# Sheet1.net
KiCad netlist of a schematic drawn in Altium Designer
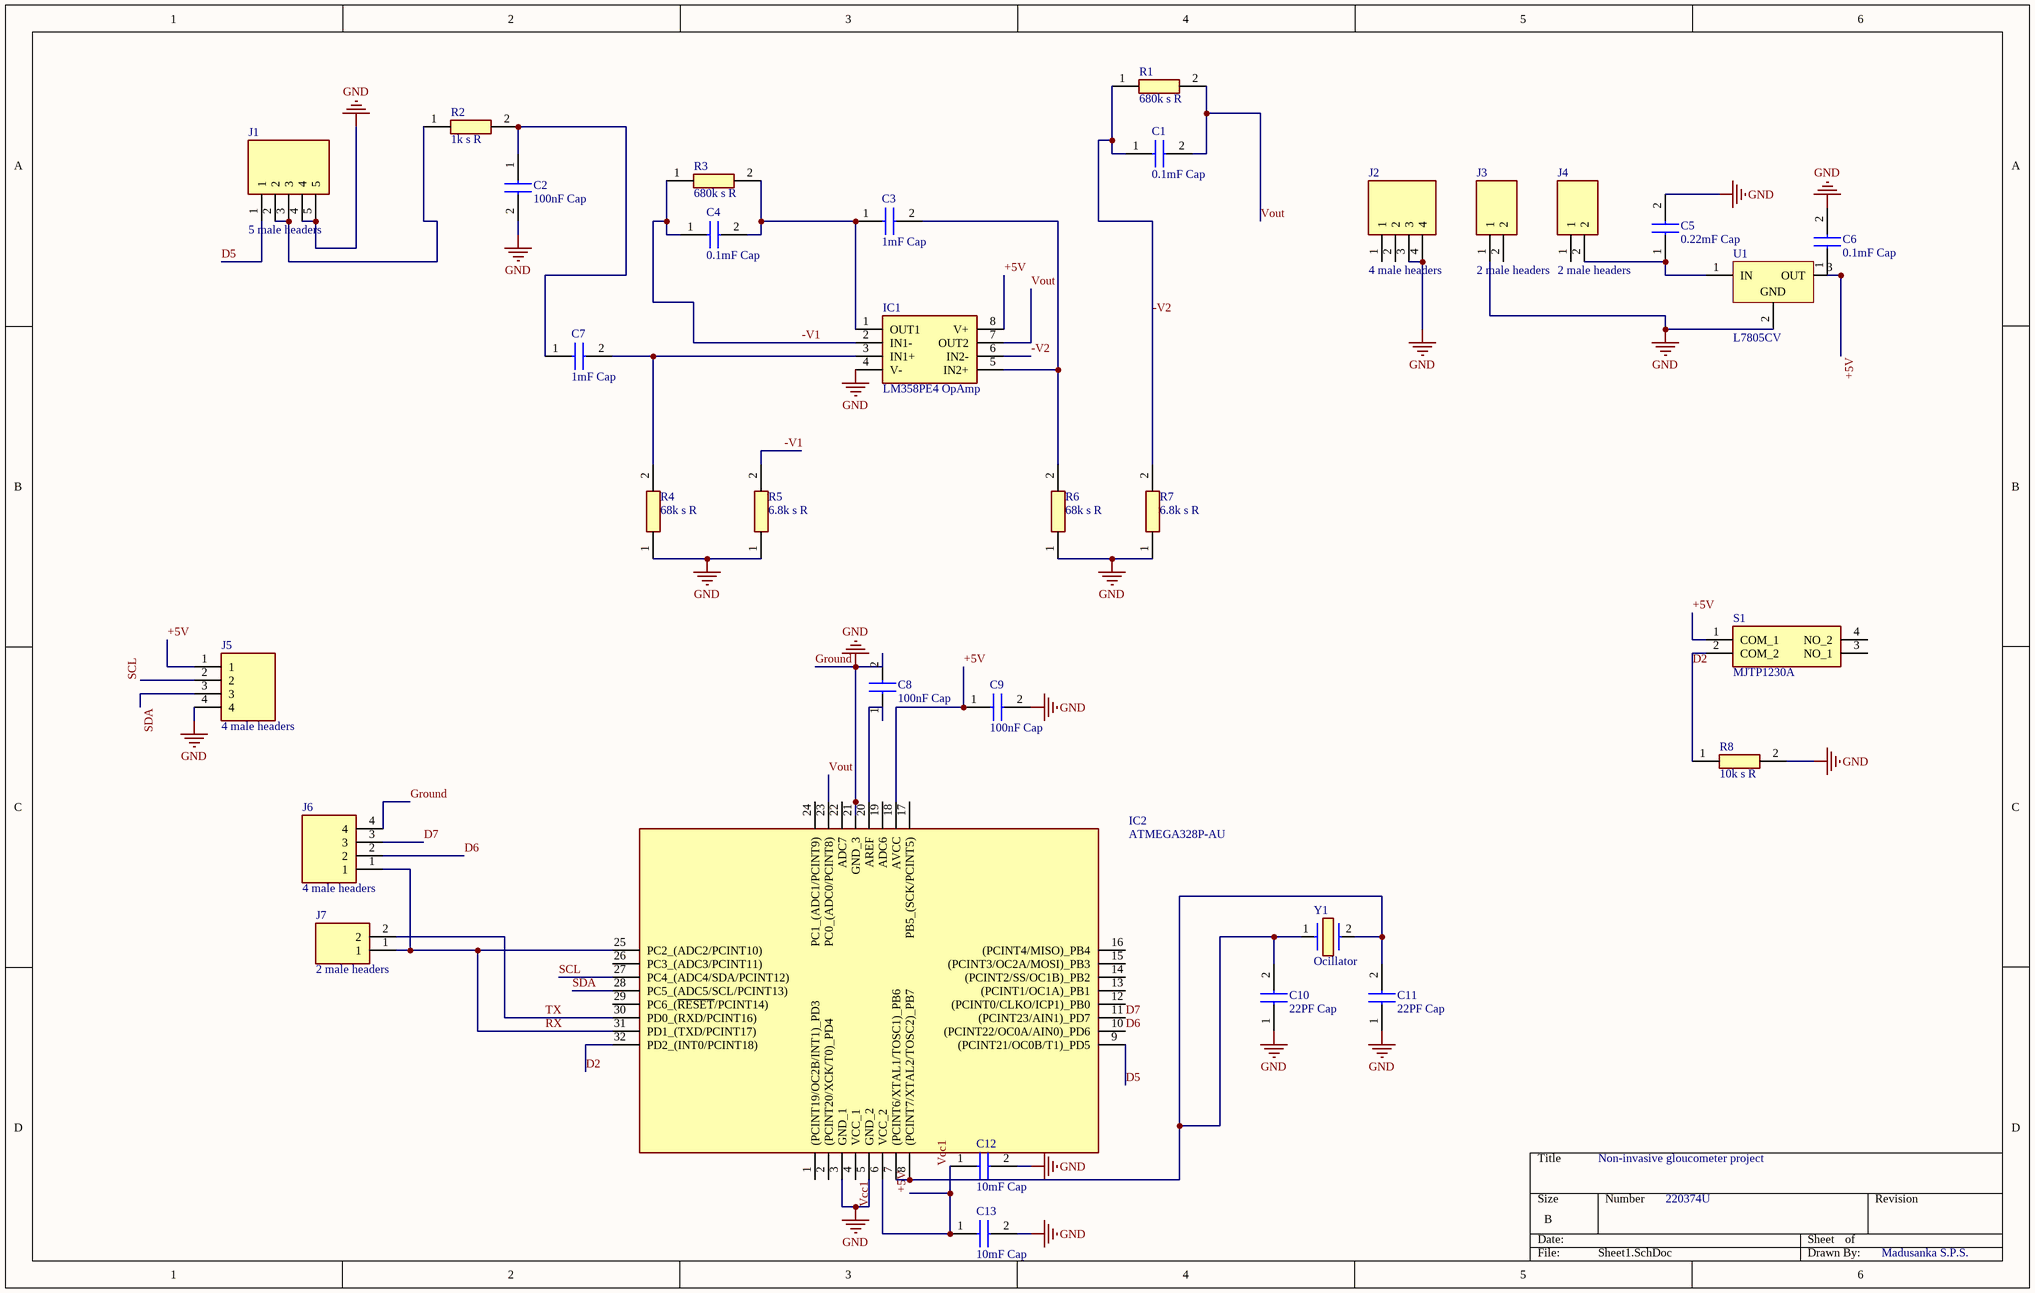
[diagram p0: Sheet1.SchDoc]

(export (version "E")
  (design (tool "Eeschema 10.0.6"))
  (components
    (comp (ref "C1")
      (value "0.1mF Cap")
      (footprint "SamacSys:VY2332M41Y5US63V7")
      (description "Capacitor")
      (fields
        (field (name "MANUFACTURER_PART_NUMBER") "VY2332M41Y5US63V7")
        (field (name "MOUSER PART NUMBER") "72-VY2332M41Y5US63V7")
      )
      (libsource (lib "Schlib1") (part "0.1mF Cap"))
    )
    (comp (ref "C2")
      (value "100nF Cap")
      (footprint "SamacSys:VY2332M41Y5US63V7")
      (description "Capacitor")
      (fields
        (field (name "MANUFACTURER_PART_NUMBER") "VY2332M41Y5US63V7")
        (field (name "MOUSER PART NUMBER") "72-VY2332M41Y5US63V7")
      )
      (libsource (lib "Schlib1") (part "100nF Cap"))
    )
    (comp (ref "C3")
      (value "1mF Cap")
      (footprint "SamacSys:VY2332M41Y5US63V7")
      (description "Capacitor")
      (fields
        (field (name "MANUFACTURER_PART_NUMBER") "VY2332M41Y5US63V7")
        (field (name "MOUSER PART NUMBER") "72-VY2332M41Y5US63V7")
      )
      (libsource (lib "Schlib1") (part "1mF Cap"))
    )
    (comp (ref "C4")
      (value "0.1mF Cap")
      (footprint "SamacSys:VY2332M41Y5US63V7")
      (description "Capacitor")
      (fields
        (field (name "MANUFACTURER_PART_NUMBER") "VY2332M41Y5US63V7")
        (field (name "MOUSER PART NUMBER") "72-VY2332M41Y5US63V7")
      )
      (libsource (lib "Schlib1") (part "0.1mF Cap"))
    )
    (comp (ref "C5")
      (value "0.22mF Cap")
      (footprint "SamacSys:VY2332M41Y5US63V7")
      (description "Capacitor")
      (fields
        (field (name "MANUFACTURER_PART_NUMBER") "VY2332M41Y5US63V7")
        (field (name "MOUSER PART NUMBER") "72-VY2332M41Y5US63V7")
      )
      (libsource (lib "Schlib1") (part "0.22mF Cap"))
    )
    (comp (ref "C6")
      (value "0.1mF Cap")
      (footprint "SamacSys:VY2332M41Y5US63V7")
      (description "Capacitor")
      (fields
        (field (name "MANUFACTURER_PART_NUMBER") "VY2332M41Y5US63V7")
        (field (name "MOUSER PART NUMBER") "72-VY2332M41Y5US63V7")
      )
      (libsource (lib "Schlib1") (part "0.1mF Cap"))
    )
    (comp (ref "C7")
      (value "1mF Cap")
      (footprint "SamacSys:VY2332M41Y5US63V7")
      (description "Capacitor")
      (fields
        (field (name "MANUFACTURER_PART_NUMBER") "VY2332M41Y5US63V7")
        (field (name "MOUSER PART NUMBER") "72-VY2332M41Y5US63V7")
      )
      (libsource (lib "Schlib1") (part "1mF Cap"))
    )
    (comp (ref "C8")
      (value "100nF Cap")
      (footprint "SamacSys:VY2332M41Y5US63V7")
      (description "Capacitor")
      (fields
        (field (name "MANUFACTURER_PART_NUMBER") "VY2332M41Y5US63V7")
        (field (name "MOUSER PART NUMBER") "72-VY2332M41Y5US63V7")
      )
      (libsource (lib "Schlib1") (part "100nF Cap"))
    )
    (comp (ref "C9")
      (value "100nF Cap")
      (footprint "SamacSys:VY2332M41Y5US63V7")
      (description "Capacitor")
      (fields
        (field (name "MANUFACTURER_PART_NUMBER") "VY2332M41Y5US63V7")
        (field (name "MOUSER PART NUMBER") "72-VY2332M41Y5US63V7")
      )
      (libsource (lib "Schlib1") (part "100nF Cap"))
    )
    (comp (ref "C10")
      (value "22PF Cap")
      (footprint "SamacSys:VY2332M41Y5US63V7")
      (description "Capacitor")
      (fields
        (field (name "MANUFACTURER_PART_NUMBER") "VY2332M41Y5US63V7")
        (field (name "MOUSER PART NUMBER") "72-VY2332M41Y5US63V7")
      )
      (libsource (lib "Schlib1") (part "22PF Cap"))
    )
    (comp (ref "C11")
      (value "22PF Cap")
      (footprint "SamacSys:VY2332M41Y5US63V7")
      (description "Capacitor")
      (fields
        (field (name "MANUFACTURER_PART_NUMBER") "VY2332M41Y5US63V7")
        (field (name "MOUSER PART NUMBER") "72-VY2332M41Y5US63V7")
      )
      (libsource (lib "Schlib1") (part "22PF Cap"))
    )
    (comp (ref "C12")
      (value "10mF Cap")
      (footprint "SamacSys:VY2332M41Y5US63V7")
      (description "Capacitor")
      (fields
        (field (name "MANUFACTURER_PART_NUMBER") "VY2332M41Y5US63V7")
        (field (name "MOUSER PART NUMBER") "72-VY2332M41Y5US63V7")
      )
      (libsource (lib "Schlib1") (part "10mF Cap"))
    )
    (comp (ref "C13")
      (value "10mF Cap")
      (footprint "SamacSys:VY2332M41Y5US63V7")
      (description "Capacitor")
      (fields
        (field (name "MANUFACTURER_PART_NUMBER") "VY2332M41Y5US63V7")
        (field (name "MOUSER PART NUMBER") "72-VY2332M41Y5US63V7")
      )
      (libsource (lib "Schlib1") (part "10mF Cap"))
    )
    (comp (ref "IC1")
      (value "LM358PE4 OpAmp")
      (footprint "SamacSys:DIP794W53P254L959H508Q8N")
      (description "Integrated Circuit")
      (fields
        (field (name "MANUFACTURER_PART_NUMBER") "LM358PE4")
        (field (name "MOUSER PART NUMBER") "595-LM358PE4")
      )
      (libsource (lib "Schlib1") (part "LM358PE4 OpAmp"))
    )
    (comp (ref "IC2")
      (value "ATMEGA328P-AU")
      (footprint "SamacSys:QFP80P900X900X120-32N")
      (description "Integrated Circuit")
      (fields (field (name "MOUSER PART NUMBER") "556-ATMEGA328P-AU"))
      (libsource (lib "Schlib1") (part "ATMEGA328P-AU"))
    )
    (comp (ref "J1")
      (value "5 male headers")
      (footprint "SamacSys:HDRV5W63P0X254_1X5_1270X254X970P")
      (description "Connector")
      (fields
        (field (name "MANUFACTURER_PART_NUMBER") "825433-5")
        (field (name "MOUSER PART NUMBER") "571-825433-5")
      )
      (libsource (lib "Schlib1") (part "5 male headers"))
    )
    (comp (ref "J2")
      (value "4 male headers")
      (footprint "SamacSys:HDRV4W63P0X254_1X4_1016X250X950P")
      (description "Connector")
      (fields
        (field (name "MANUFACTURER_PART_NUMBER") "826629-4")
        (field (name "MOUSER PART NUMBER") "571-826629-4")
      )
      (libsource (lib "Schlib1") (part "4 male headers"))
    )
    (comp (ref "J3")
      (value "2 male headers")
      (footprint "SamacSys:HDRV2W63P0X254_1X2_508X250X970P")
      (description "Connector")
      (fields
        (field (name "MANUFACTURER_PART_NUMBER") "826926-2")
        (field (name "MOUSER PART NUMBER") "571-826926-2")
      )
      (libsource (lib "") (part "2 male headers_1"))
    )
    (comp (ref "J4")
      (value "2 male headers")
      (footprint "SamacSys:HDRV2W63P0X254_1X2_508X250X970P")
      (description "Connector")
      (fields
        (field (name "MANUFACTURER_PART_NUMBER") "826926-2")
        (field (name "MOUSER PART NUMBER") "571-826926-2")
      )
      (libsource (lib "") (part "2 male headers_1"))
    )
    (comp (ref "J5")
      (value "4 male headers")
      (footprint "SamacSys:HDRV4W63P0X254_1X4_1016X250X950P")
      (description "Connector")
      (fields
        (field (name "MANUFACTURER_PART_NUMBER") "826629-4")
        (field (name "MOUSER PART NUMBER") "571-826629-4")
      )
      (libsource (lib "") (part "4 male headers_2"))
    )
    (comp (ref "J6")
      (value "4 male headers")
      (footprint "SamacSys:HDRV4W63P0X254_1X4_1016X250X950P")
      (description "Connector")
      (fields
        (field (name "MANUFACTURER_PART_NUMBER") "826629-4")
        (field (name "MOUSER PART NUMBER") "571-826629-4")
      )
      (libsource (lib "") (part "4 male headers_1"))
    )
    (comp (ref "J7")
      (value "2 male headers")
      (footprint "SamacSys:HDRV2W63P0X254_1X2_508X250X970P")
      (description "Connector")
      (fields
        (field (name "MANUFACTURER_PART_NUMBER") "826926-2")
        (field (name "MOUSER PART NUMBER") "571-826926-2")
      )
      (libsource (lib "Schlib1") (part "2 male headers"))
    )
    (comp (ref "R1")
      (value "680k s R")
      (footprint "SamacSys:ERJUP6")
      (description "Resistor")
      (fields
        (field (name "MANUFACTURER_PART_NUMBER") "ERJ-UP6F5760V")
        (field (name "MOUSER PART NUMBER") "667-ERJ-UP6F5760V")
      )
      (libsource (lib "Schlib1") (part "680k s R"))
    )
    (comp (ref "R2")
      (value "1k s R")
      (footprint "SamacSys:ERJUP6")
      (description "Resistor")
      (fields
        (field (name "MANUFACTURER_PART_NUMBER") "ERJ-UP6F5760V")
        (field (name "MOUSER PART NUMBER") "667-ERJ-UP6F5760V")
      )
      (libsource (lib "Schlib1") (part "1k s R"))
    )
    (comp (ref "R3")
      (value "680k s R")
      (footprint "SamacSys:ERJUP6")
      (description "Resistor")
      (fields
        (field (name "MANUFACTURER_PART_NUMBER") "ERJ-UP6F5760V")
        (field (name "MOUSER PART NUMBER") "667-ERJ-UP6F5760V")
      )
      (libsource (lib "Schlib1") (part "680k s R"))
    )
    (comp (ref "R4")
      (value "68k s R")
      (footprint "SamacSys:ERJUP6")
      (description "Resistor")
      (fields
        (field (name "MANUFACTURER_PART_NUMBER") "ERJ-UP6F5760V")
        (field (name "MOUSER PART NUMBER") "667-ERJ-UP6F5760V")
      )
      (libsource (lib "Schlib1") (part "68k s R"))
    )
    (comp (ref "R5")
      (value "6.8k s R")
      (footprint "SamacSys:ERJUP6")
      (description "Resistor")
      (fields
        (field (name "MANUFACTURER_PART_NUMBER") "ERJ-UP6F5760V")
        (field (name "MOUSER PART NUMBER") "667-ERJ-UP6F5760V")
      )
      (libsource (lib "Schlib1") (part "6.8k s R"))
    )
    (comp (ref "R6")
      (value "68k s R")
      (footprint "SamacSys:ERJUP6")
      (description "Resistor")
      (fields
        (field (name "MANUFACTURER_PART_NUMBER") "ERJ-UP6F5760V")
        (field (name "MOUSER PART NUMBER") "667-ERJ-UP6F5760V")
      )
      (libsource (lib "Schlib1") (part "68k s R"))
    )
    (comp (ref "R7")
      (value "6.8k s R")
      (footprint "SamacSys:ERJUP6")
      (description "Resistor")
      (fields
        (field (name "MANUFACTURER_PART_NUMBER") "ERJ-UP6F5760V")
        (field (name "MOUSER PART NUMBER") "667-ERJ-UP6F5760V")
      )
      (libsource (lib "Schlib1") (part "6.8k s R"))
    )
    (comp (ref "R8")
      (value "10k s R")
      (footprint "SamacSys:ERJUP6")
      (description "Resistor")
      (fields
        (field (name "MANUFACTURER_PART_NUMBER") "ERJ-UP6F5760V")
        (field (name "MOUSER PART NUMBER") "667-ERJ-UP6F5760V")
      )
      (libsource (lib "Schlib1") (part "10k s R"))
    )
    (comp (ref "S1")
      (value "MJTP1230A")
      (footprint "SamacSys:MJTP1230A")
      (description "Switch")
      (fields (field (name "MOUSER PART NUMBER") "642-MJTP1230A"))
      (libsource (lib "Schlib1") (part "MJTP1230A"))
    )
    (comp (ref "U1")
      (value "L7805CV")
      (footprint "TO220")
      (description "Positive Voltage Regulator, 5V, 3-Pin TO-220")
      (libsource (lib "Altium Content Vault") (part "PM-REG-L4940-SIL3"))
    )
    (comp (ref "Y1")
      (value "Ocillator")
      (footprint "SamacSys:XT9S20ANA8M")
      (description "Crystal or Oscillator")
      (fields
        (field (name "MANUFACTURER_PART_NUMBER") "XT9S20ANA8M")
        (field (name "MOUSER PART NUMBER") "73-XT49S800-20")
      )
      (libsource (lib "Schlib1") (part "Ocillator"))
    )
  )
  (nets
    (net (code "1") (name "/+5V") (class "Default")
      (node (ref "C12") (pin "1") (pinfunction "1_1") (pintype "passive"))
      (node (ref "C13") (pin "1") (pinfunction "1_1") (pintype "passive"))
      (node (ref "C6") (pin "1") (pinfunction "1_1") (pintype "passive"))
      (node (ref "C9") (pin "1") (pinfunction "1_1") (pintype "passive"))
      (node (ref "IC1") (pin "8") (pinfunction "V+_8") (pintype "passive"))
      (node (ref "IC2") (pin "18") (pinfunction "AVCC_18") (pintype "passive"))
      (node (ref "IC2") (pin "4") (pinfunction "VCC_1_4") (pintype "passive"))
      (node (ref "IC2") (pin "6") (pinfunction "VCC_2_6") (pintype "passive"))
      (node (ref "J5") (pin "1") (pinfunction "1_1") (pintype "passive"))
      (node (ref "S1") (pin "1") (pinfunction "COM_1_1") (pintype "passive"))
      (node (ref "U1") (pin "3") (pinfunction "OUT_3") (pintype "power_in"))
    )
    (net (code "2") (name "/-V1") (class "Default")
      (node (ref "C4") (pin "1") (pinfunction "1_1") (pintype "passive"))
      (node (ref "IC1") (pin "2") (pinfunction "IN1-_2") (pintype "passive"))
      (node (ref "R3") (pin "1") (pinfunction "1_1") (pintype "passive"))
      (node (ref "R5") (pin "2") (pinfunction "2_2") (pintype "passive"))
    )
    (net (code "3") (name "/-V2") (class "Default")
      (node (ref "C1") (pin "1") (pinfunction "1_1") (pintype "passive"))
      (node (ref "IC1") (pin "6") (pinfunction "IN2-_6") (pintype "passive"))
      (node (ref "R1") (pin "1") (pinfunction "1_1") (pintype "passive"))
      (node (ref "R7") (pin "2") (pinfunction "2_2") (pintype "passive"))
    )
    (net (code "4") (name "/D2") (class "Default")
      (node (ref "IC2") (pin "32") (pinfunction "PD2_(INT0/PCINT18)_32") (pintype "passive"))
      (node (ref "R8") (pin "1") (pinfunction "1_1") (pintype "passive"))
      (node (ref "S1") (pin "2") (pinfunction "COM_2_2") (pintype "passive"))
    )
    (net (code "5") (name "/D5") (class "Default")
      (node (ref "IC2") (pin "9") (pinfunction "(PCINT21/OC0B/T1)_PD5_9") (pintype "passive"))
      (node (ref "J1") (pin "1") (pinfunction "1_1") (pintype "passive"))
    )
    (net (code "6") (name "/D6") (class "Default")
      (node (ref "IC2") (pin "10") (pinfunction "(PCINT22/OC0A/AIN0)_PD6_10") (pintype "passive"))
      (node (ref "J6") (pin "2") (pinfunction "2_2") (pintype "passive"))
    )
    (net (code "7") (name "/D7") (class "Default")
      (node (ref "IC2") (pin "11") (pinfunction "(PCINT23/AIN1)_PD7_11") (pintype "passive"))
      (node (ref "J6") (pin "3") (pinfunction "3_3") (pintype "passive"))
    )
    (net (code "8") (name "/RX") (class "Default")
      (node (ref "IC2") (pin "25") (pinfunction "PC2_(ADC2/PCINT10)_25") (pintype "passive"))
      (node (ref "IC2") (pin "31") (pinfunction "PD1_(TXD/PCINT17)_31") (pintype "passive"))
      (node (ref "J6") (pin "1") (pinfunction "1_1") (pintype "passive"))
      (node (ref "J7") (pin "1") (pinfunction "1_1") (pintype "passive"))
    )
    (net (code "9") (name "/SCL") (class "Default")
      (node (ref "IC2") (pin "27") (pinfunction "PC4_(ADC4/SDA/PCINT12)_27") (pintype "passive"))
      (node (ref "J5") (pin "2") (pinfunction "2_2") (pintype "passive"))
    )
    (net (code "10") (name "/SDA") (class "Default")
      (node (ref "IC2") (pin "28") (pinfunction "PC5_(ADC5/SCL/PCINT13)_28") (pintype "passive"))
      (node (ref "J5") (pin "3") (pinfunction "3_3") (pintype "passive"))
    )
    (net (code "11") (name "/TX") (class "Default")
      (node (ref "IC2") (pin "30") (pinfunction "PD0_(RXD/PCINT16)_30") (pintype "passive"))
      (node (ref "J7") (pin "2") (pinfunction "2_2") (pintype "passive"))
    )
    (net (code "12") (name "/Vout") (class "Default")
      (node (ref "C1") (pin "2") (pinfunction "2_2") (pintype "passive"))
      (node (ref "IC1") (pin "7") (pinfunction "OUT2_7") (pintype "passive"))
      (node (ref "IC2") (pin "23") (pinfunction "PC0_(ADC0/PCINT8)_23") (pintype "passive"))
      (node (ref "R1") (pin "2") (pinfunction "2_2") (pintype "passive"))
    )
    (net (code "13") (name "GND") (class "Default")
      (node (ref "C10") (pin "1") (pinfunction "1_1") (pintype "passive"))
      (node (ref "C11") (pin "1") (pinfunction "1_1") (pintype "passive"))
      (node (ref "C12") (pin "2") (pinfunction "2_2") (pintype "passive"))
      (node (ref "C13") (pin "2") (pinfunction "2_2") (pintype "passive"))
      (node (ref "C2") (pin "2") (pinfunction "2_2") (pintype "passive"))
      (node (ref "C5") (pin "2") (pinfunction "2_2") (pintype "passive"))
      (node (ref "C6") (pin "2") (pinfunction "2_2") (pintype "passive"))
      (node (ref "C8") (pin "2") (pinfunction "2_2") (pintype "passive"))
      (node (ref "C9") (pin "2") (pinfunction "2_2") (pintype "passive"))
      (node (ref "IC1") (pin "4") (pinfunction "V-_4") (pintype "passive"))
      (node (ref "IC2") (pin "21") (pinfunction "GND_3_21") (pintype "passive"))
      (node (ref "IC2") (pin "3") (pinfunction "GND_1_3") (pintype "passive"))
      (node (ref "IC2") (pin "5") (pinfunction "GND_2_5") (pintype "passive"))
      (node (ref "J1") (pin "4") (pinfunction "4_4") (pintype "passive"))
      (node (ref "J1") (pin "5") (pinfunction "5_5") (pintype "passive"))
      (node (ref "J2") (pin "3") (pinfunction "3_3") (pintype "passive"))
      (node (ref "J2") (pin "4") (pinfunction "4_4") (pintype "passive"))
      (node (ref "J3") (pin "1") (pinfunction "1_1") (pintype "passive"))
      (node (ref "J5") (pin "4") (pinfunction "4_4") (pintype "passive"))
      (node (ref "J6") (pin "4") (pinfunction "4_4") (pintype "passive"))
      (node (ref "R4") (pin "1") (pinfunction "1_1") (pintype "passive"))
      (node (ref "R5") (pin "1") (pinfunction "1_1") (pintype "passive"))
      (node (ref "R6") (pin "1") (pinfunction "1_1") (pintype "passive"))
      (node (ref "R7") (pin "1") (pinfunction "1_1") (pintype "passive"))
      (node (ref "R8") (pin "2") (pinfunction "2_2") (pintype "passive"))
      (node (ref "U1") (pin "2") (pinfunction "GND_2") (pintype "power_in"))
    )
    (net (code "14") (name "Net-(C2-Pad1)") (class "Default")
      (node (ref "C2") (pin "1") (pinfunction "1_1") (pintype "passive"))
      (node (ref "C7") (pin "1") (pinfunction "1_1") (pintype "passive"))
      (node (ref "R2") (pin "2") (pinfunction "2_2") (pintype "passive"))
    )
    (net (code "15") (name "Net-(IC1-IN1+)") (class "Default")
      (node (ref "C7") (pin "2") (pinfunction "2_2") (pintype "passive"))
      (node (ref "IC1") (pin "3") (pinfunction "IN1+_3") (pintype "passive"))
      (node (ref "R4") (pin "2") (pinfunction "2_2") (pintype "passive"))
    )
    (net (code "16") (name "Net-(IC1-IN2+)") (class "Default")
      (node (ref "C3") (pin "2") (pinfunction "2_2") (pintype "passive"))
      (node (ref "IC1") (pin "5") (pinfunction "IN2+_5") (pintype "passive"))
      (node (ref "R6") (pin "2") (pinfunction "2_2") (pintype "passive"))
    )
    (net (code "17") (name "Net-(IC1-OUT1)") (class "Default")
      (node (ref "C3") (pin "1") (pinfunction "1_1") (pintype "passive"))
      (node (ref "C4") (pin "2") (pinfunction "2_2") (pintype "passive"))
      (node (ref "IC1") (pin "1") (pinfunction "OUT1_1") (pintype "passive"))
      (node (ref "R3") (pin "2") (pinfunction "2_2") (pintype "passive"))
    )
    (net (code "18") (name "Net-(IC2-(PCINT6{slash}XTAL1{slash}TOSC1)_PB6)") (class "Default")
      (node (ref "C10") (pin "2") (pinfunction "2_2") (pintype "passive"))
      (node (ref "C11") (pin "2") (pinfunction "2_2") (pintype "passive"))
      (node (ref "IC2") (pin "7") (pinfunction "(PCINT6/XTAL1/TOSC1)_PB6_7") (pintype "passive"))
      (node (ref "IC2") (pin "8") (pinfunction "(PCINT7/XTAL2/TOSC2)_PB7_8") (pintype "passive"))
      (node (ref "Y1") (pin "1") (pinfunction "1_1") (pintype "passive"))
      (node (ref "Y1") (pin "2") (pinfunction "2_2") (pintype "passive"))
    )
    (net (code "19") (name "Net-(IC2-AREF)") (class "Default")
      (node (ref "C8") (pin "1") (pinfunction "1_1") (pintype "passive"))
      (node (ref "IC2") (pin "20") (pinfunction "AREF_20") (pintype "passive"))
    )
    (net (code "20") (name "Net-(J1-Pad2)") (class "Default")
      (node (ref "J1") (pin "2") (pinfunction "2_2") (pintype "passive"))
      (node (ref "J1") (pin "3") (pinfunction "3_3") (pintype "passive"))
      (node (ref "R2") (pin "1") (pinfunction "1_1") (pintype "passive"))
    )
    (net (code "21") (name "Net-(U1-IN)") (class "Default")
      (node (ref "C5") (pin "1") (pinfunction "1_1") (pintype "passive"))
      (node (ref "J4") (pin "2") (pinfunction "2_2") (pintype "passive"))
      (node (ref "U1") (pin "1") (pinfunction "IN_1") (pintype "power_in"))
    )
    (net (code "22") (name "unconnected-(IC2-(PCINT0{slash}CLKO{slash}ICP1)_PB0-Pad12)") (class "Default")
      (node (ref "IC2") (pin "12") (pinfunction "(PCINT0/CLKO/ICP1)_PB0_12") (pintype "passive"))
    )
    (net (code "23") (name "unconnected-(IC2-(PCINT1{slash}OC1A)_PB1-Pad13)") (class "Default")
      (node (ref "IC2") (pin "13") (pinfunction "(PCINT1/OC1A)_PB1_13") (pintype "passive"))
    )
    (net (code "24") (name "unconnected-(IC2-(PCINT2{slash}SS{slash}OC1B)_PB2-Pad14)") (class "Default")
      (node (ref "IC2") (pin "14") (pinfunction "(PCINT2/SS/OC1B)_PB2_14") (pintype "passive"))
    )
    (net (code "25") (name "unconnected-(IC2-(PCINT3{slash}OC2A{slash}MOSI)_PB3-Pad15)") (class "Default")
      (node (ref "IC2") (pin "15") (pinfunction "(PCINT3/OC2A/MOSI)_PB3_15") (pintype "passive"))
    )
    (net (code "26") (name "unconnected-(IC2-(PCINT4{slash}MISO)_PB4-Pad16)") (class "Default")
      (node (ref "IC2") (pin "16") (pinfunction "(PCINT4/MISO)_PB4_16") (pintype "passive"))
    )
    (net (code "27") (name "unconnected-(IC2-(PCINT19{slash}OC2B{slash}INT1)_PD3-Pad1)") (class "Default")
      (node (ref "IC2") (pin "1") (pinfunction "(PCINT19/OC2B/INT1)_PD3_1") (pintype "passive"))
    )
    (net (code "28") (name "unconnected-(IC2-(PCINT20{slash}XCK{slash}T0)_PD4-Pad2)") (class "Default")
      (node (ref "IC2") (pin "2") (pinfunction "(PCINT20/XCK/T0)_PD4_2") (pintype "passive"))
    )
    (net (code "29") (name "unconnected-(IC2-ADC6-Pad19)") (class "Default")
      (node (ref "IC2") (pin "19") (pinfunction "ADC6_19") (pintype "passive"))
    )
    (net (code "30") (name "unconnected-(IC2-ADC7-Pad22)") (class "Default")
      (node (ref "IC2") (pin "22") (pinfunction "ADC7_22") (pintype "passive"))
    )
    (net (code "31") (name "unconnected-(IC2-PB5_(SCK{slash}PCINT5)-Pad17)") (class "Default")
      (node (ref "IC2") (pin "17") (pinfunction "PB5_(SCK/PCINT5)_17") (pintype "passive"))
    )
    (net (code "32") (name "unconnected-(IC2-PC1_(ADC1{slash}PCINT9)-Pad24)") (class "Default")
      (node (ref "IC2") (pin "24") (pinfunction "PC1_(ADC1/PCINT9)_24") (pintype "passive"))
    )
    (net (code "33") (name "unconnected-(IC2-PC3_(ADC3{slash}PCINT11)-Pad26)") (class "Default")
      (node (ref "IC2") (pin "26") (pinfunction "PC3_(ADC3/PCINT11)_26") (pintype "passive"))
    )
    (net (code "34") (name "unconnected-(IC2-PC6_(~{RESET}{slash}PCINT14)-Pad29)") (class "Default")
      (node (ref "IC2") (pin "29") (pinfunction "PC6_(~{RESET}/PCINT14)_29") (pintype "passive"))
    )
    (net (code "35") (name "unconnected-(J2-Pad1)") (class "Default")
      (node (ref "J2") (pin "1") (pinfunction "1_1") (pintype "passive"))
    )
    (net (code "36") (name "unconnected-(J2-Pad2)") (class "Default")
      (node (ref "J2") (pin "2") (pinfunction "2_2") (pintype "passive"))
    )
    (net (code "37") (name "unconnected-(J3-Pad2)") (class "Default")
      (node (ref "J3") (pin "2") (pinfunction "2_2") (pintype "passive"))
    )
    (net (code "38") (name "unconnected-(J4-Pad1)") (class "Default")
      (node (ref "J4") (pin "1") (pinfunction "1_1") (pintype "passive"))
    )
    (net (code "39") (name "unconnected-(S1-NO_1-Pad3)") (class "Default")
      (node (ref "S1") (pin "3") (pinfunction "NO_1_3") (pintype "passive"))
    )
    (net (code "40") (name "unconnected-(S1-NO_2-Pad4)") (class "Default")
      (node (ref "S1") (pin "4") (pinfunction "NO_2_4") (pintype "passive"))
    )
  )
)
